# tubeamplights.net
KiCad netlist of a schematic drawn in EAGLE
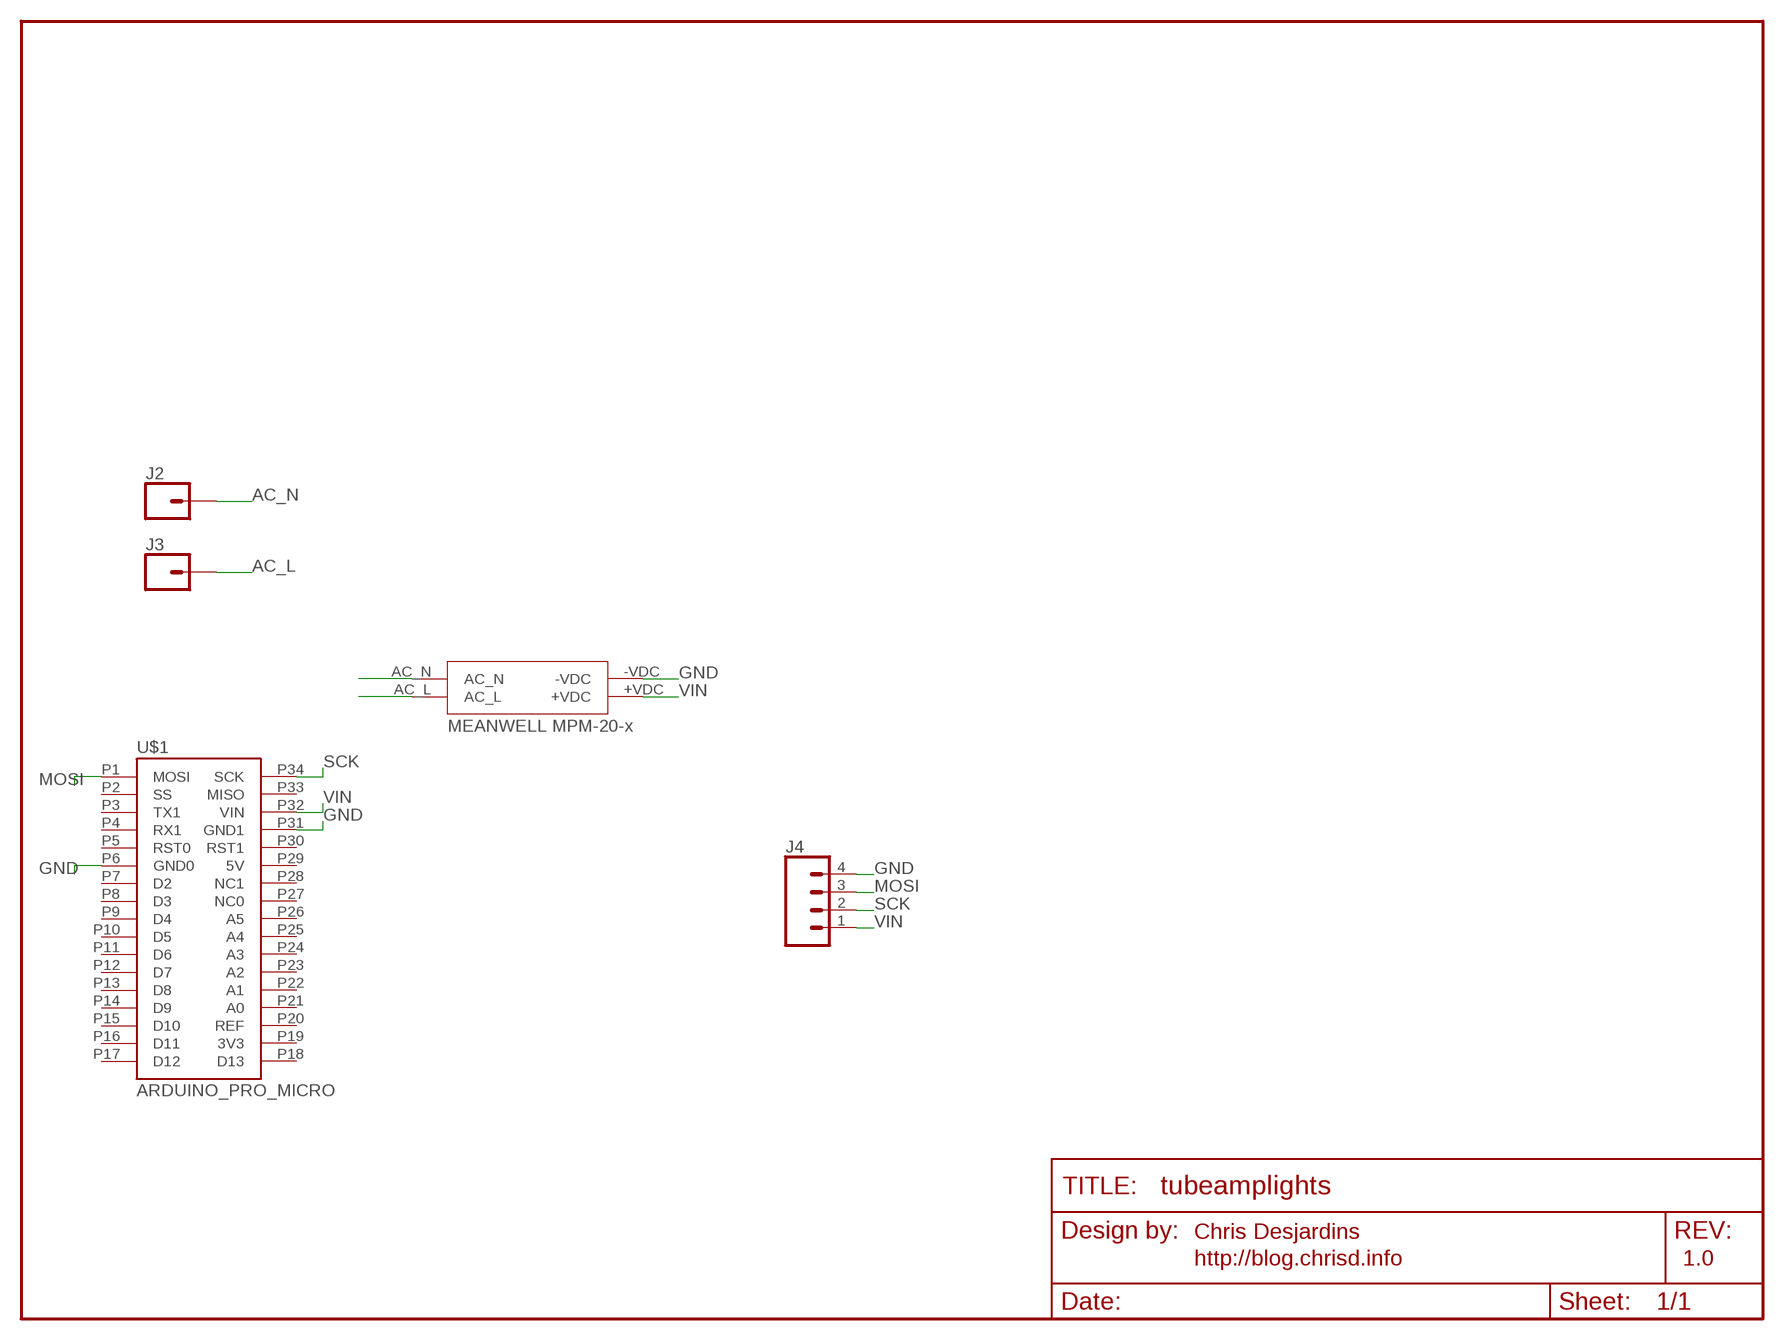
[diagram p0: schematic, sheet 1]

(export (version "E")
  (design (tool "Eeschema 10.0.6"))
  (components
    (comp (ref "J2")
      (value "CONN_01PTH_2MM")
      (footprint "eagle-import:1X01_2MM")
      (libsource (lib "eagle-import") (part "CONN_01PTH_2MM"))
    )
    (comp (ref "J3")
      (value "CONN_01PTH_2MM")
      (footprint "eagle-import:1X01_2MM")
      (libsource (lib "eagle-import") (part "CONN_01PTH_2MM"))
    )
    (comp (ref "J4")
      (value "CONN_04")
      (footprint "eagle-import:1X04")
      (libsource (lib "eagle-import") (part "CONN_04"))
    )
    (comp (ref "U$1")
      (value "ARDUINO_PRO_MICRO")
      (footprint "eagle-import:ARDUINO_PRO_MICRO")
      (libsource (lib "eagle-import") (part "ARDUINO_PRO_MICRO"))
    )
    (comp (ref "U$2")
      (value "MPM-20-X")
      (footprint "eagle-import:MPM-20-X")
      (libsource (lib "eagle-import") (part "MPM-20-X"))
    )
  )
  (nets
    (net (code "1") (name "/3V3") (class "Default")
      (node (ref "U$1") (pin "P19") (pinfunction "3V3_P19") (pintype "power_in"))
    )
    (net (code "2") (name "/5V") (class "Default")
      (node (ref "U$1") (pin "P29") (pinfunction "5V_P29") (pintype "power_in"))
    )
    (net (code "3") (name "/AC_L") (class "Default")
      (node (ref "J3") (pin "1") (pinfunction "1_1") (pintype "passive"))
      (node (ref "U$2") (pin "AC_L") (pinfunction "AC_L_AC_L") (pintype "bidirectional"))
    )
    (net (code "4") (name "/AC_N") (class "Default")
      (node (ref "J2") (pin "1") (pinfunction "1_1") (pintype "passive"))
      (node (ref "U$2") (pin "AC_N") (pinfunction "AC_N_AC_N") (pintype "bidirectional"))
    )
    (net (code "5") (name "/GND") (class "Default")
      (node (ref "J4") (pin "4") (pinfunction "4_4") (pintype "passive"))
      (node (ref "U$1") (pin "P31") (pinfunction "GND1_P31") (pintype "power_in"))
      (node (ref "U$1") (pin "P6") (pinfunction "GND0_P6") (pintype "power_in"))
      (node (ref "U$2") (pin "-VDC") (pinfunction "-VDC_-VDC") (pintype "bidirectional"))
    )
    (net (code "6") (name "/MOSI") (class "Default")
      (node (ref "J4") (pin "3") (pinfunction "3_3") (pintype "passive"))
      (node (ref "U$1") (pin "P1") (pinfunction "MOSI_P1") (pintype "bidirectional"))
    )
    (net (code "7") (name "/REF") (class "Default")
      (node (ref "U$1") (pin "P20") (pinfunction "REF_P20") (pintype "power_in"))
    )
    (net (code "8") (name "/SCK") (class "Default")
      (node (ref "J4") (pin "2") (pinfunction "2_2") (pintype "passive"))
      (node (ref "U$1") (pin "P34") (pinfunction "SCK_P34") (pintype "bidirectional"))
    )
    (net (code "9") (name "/VIN") (class "Default")
      (node (ref "J4") (pin "1") (pinfunction "1_1") (pintype "passive"))
      (node (ref "U$1") (pin "P32") (pinfunction "VIN_P32") (pintype "power_in"))
      (node (ref "U$2") (pin "+VDC") (pinfunction "+VDC_+VDC") (pintype "bidirectional"))
    )
    (net (code "10") (name "unconnected-(U$1-A0-PadP21)") (class "Default")
      (node (ref "U$1") (pin "P21") (pinfunction "A0_P21") (pintype "bidirectional"))
    )
    (net (code "11") (name "unconnected-(U$1-A1-PadP22)") (class "Default")
      (node (ref "U$1") (pin "P22") (pinfunction "A1_P22") (pintype "bidirectional"))
    )
    (net (code "12") (name "unconnected-(U$1-A2-PadP23)") (class "Default")
      (node (ref "U$1") (pin "P23") (pinfunction "A2_P23") (pintype "bidirectional"))
    )
    (net (code "13") (name "unconnected-(U$1-A3-PadP24)") (class "Default")
      (node (ref "U$1") (pin "P24") (pinfunction "A3_P24") (pintype "bidirectional"))
    )
    (net (code "14") (name "unconnected-(U$1-A4-PadP25)") (class "Default")
      (node (ref "U$1") (pin "P25") (pinfunction "A4_P25") (pintype "bidirectional"))
    )
    (net (code "15") (name "unconnected-(U$1-A5-PadP26)") (class "Default")
      (node (ref "U$1") (pin "P26") (pinfunction "A5_P26") (pintype "bidirectional"))
    )
    (net (code "16") (name "unconnected-(U$1-D2-PadP7)") (class "Default")
      (node (ref "U$1") (pin "P7") (pinfunction "D2_P7") (pintype "bidirectional"))
    )
    (net (code "17") (name "unconnected-(U$1-D3-PadP8)") (class "Default")
      (node (ref "U$1") (pin "P8") (pinfunction "D3_P8") (pintype "bidirectional"))
    )
    (net (code "18") (name "unconnected-(U$1-D4-PadP9)") (class "Default")
      (node (ref "U$1") (pin "P9") (pinfunction "D4_P9") (pintype "bidirectional"))
    )
    (net (code "19") (name "unconnected-(U$1-D5-PadP10)") (class "Default")
      (node (ref "U$1") (pin "P10") (pinfunction "D5_P10") (pintype "bidirectional"))
    )
    (net (code "20") (name "unconnected-(U$1-D6-PadP11)") (class "Default")
      (node (ref "U$1") (pin "P11") (pinfunction "D6_P11") (pintype "bidirectional"))
    )
    (net (code "21") (name "unconnected-(U$1-D7-PadP12)") (class "Default")
      (node (ref "U$1") (pin "P12") (pinfunction "D7_P12") (pintype "bidirectional"))
    )
    (net (code "22") (name "unconnected-(U$1-D8-PadP13)") (class "Default")
      (node (ref "U$1") (pin "P13") (pinfunction "D8_P13") (pintype "bidirectional"))
    )
    (net (code "23") (name "unconnected-(U$1-D9-PadP14)") (class "Default")
      (node (ref "U$1") (pin "P14") (pinfunction "D9_P14") (pintype "bidirectional"))
    )
    (net (code "24") (name "unconnected-(U$1-D10-PadP15)") (class "Default")
      (node (ref "U$1") (pin "P15") (pinfunction "D10_P15") (pintype "bidirectional"))
    )
    (net (code "25") (name "unconnected-(U$1-D11-PadP16)") (class "Default")
      (node (ref "U$1") (pin "P16") (pinfunction "D11_P16") (pintype "bidirectional"))
    )
    (net (code "26") (name "unconnected-(U$1-D12-PadP17)") (class "Default")
      (node (ref "U$1") (pin "P17") (pinfunction "D12_P17") (pintype "bidirectional"))
    )
    (net (code "27") (name "unconnected-(U$1-D13-PadP18)") (class "Default")
      (node (ref "U$1") (pin "P18") (pinfunction "D13_P18") (pintype "bidirectional"))
    )
    (net (code "28") (name "unconnected-(U$1-MISO-PadP33)") (class "Default")
      (node (ref "U$1") (pin "P33") (pinfunction "MISO_P33") (pintype "bidirectional"))
    )
    (net (code "29") (name "unconnected-(U$1-NC0-PadP27)") (class "Default")
      (node (ref "U$1") (pin "P27") (pinfunction "NC0_P27") (pintype "no_connect"))
    )
    (net (code "30") (name "unconnected-(U$1-NC1-PadP28)") (class "Default")
      (node (ref "U$1") (pin "P28") (pinfunction "NC1_P28") (pintype "no_connect"))
    )
    (net (code "31") (name "unconnected-(U$1-RST0-PadP5)") (class "Default")
      (node (ref "U$1") (pin "P5") (pinfunction "RST0_P5") (pintype "bidirectional"))
    )
    (net (code "32") (name "unconnected-(U$1-RST1-PadP30)") (class "Default")
      (node (ref "U$1") (pin "P30") (pinfunction "RST1_P30") (pintype "bidirectional"))
    )
    (net (code "33") (name "unconnected-(U$1-RX1-PadP4)") (class "Default")
      (node (ref "U$1") (pin "P4") (pinfunction "RX1_P4") (pintype "bidirectional"))
    )
    (net (code "34") (name "unconnected-(U$1-SS-PadP2)") (class "Default")
      (node (ref "U$1") (pin "P2") (pinfunction "SS_P2") (pintype "bidirectional"))
    )
    (net (code "35") (name "unconnected-(U$1-TX1-PadP3)") (class "Default")
      (node (ref "U$1") (pin "P3") (pinfunction "TX1_P3") (pintype "bidirectional"))
    )
  )
)
